# 3V3-CAN-UNISOLATED.net
KiCad netlist of a schematic drawn in Altium Designer
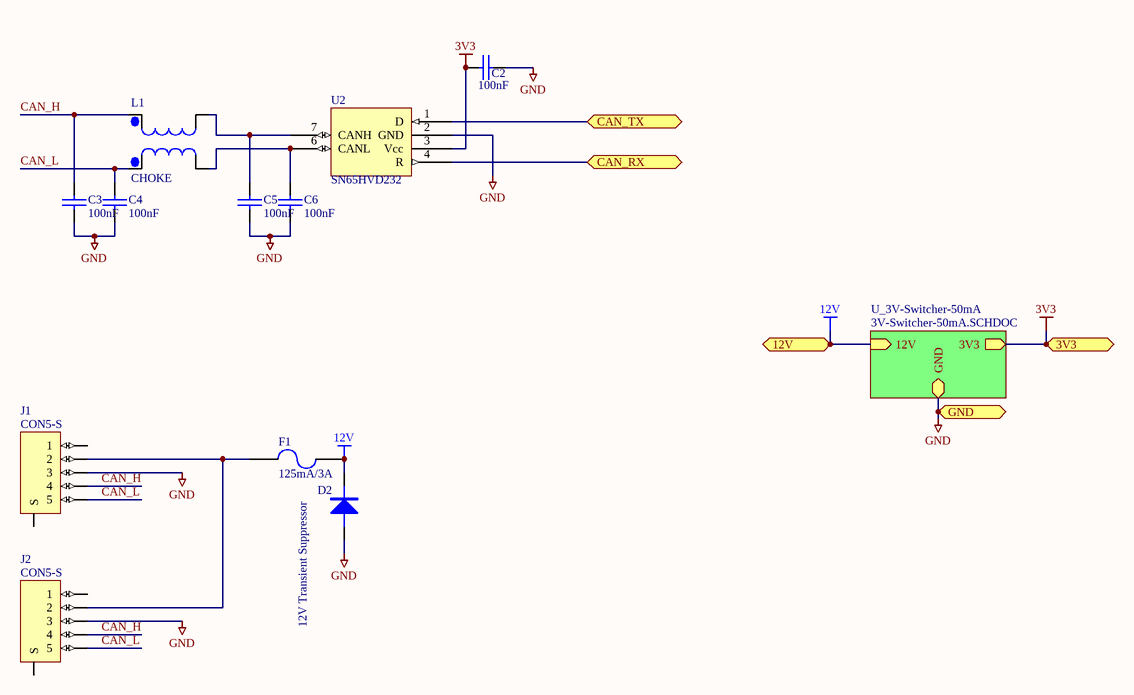
[diagram p0: 3V3-CAN-UNISOLATED.SchDoc]

(export (version "E")
  (design (tool "Eeschema 10.0.6"))
  (components
    (comp (ref "C2")
      (value "100nF")
      (footprint "0603")
      (description "Capacitor")
      (libsource (lib "*") (part "CAP"))
    )
    (comp (ref "C3")
      (value "100nF")
      (footprint "0603")
      (description "Capacitor")
      (libsource (lib "*") (part "CAP"))
    )
    (comp (ref "C4")
      (value "100nF")
      (footprint "0603")
      (description "Capacitor")
      (libsource (lib "*") (part "CAP"))
    )
    (comp (ref "C5")
      (value "100nF")
      (footprint "0603")
      (description "Capacitor")
      (libsource (lib "*") (part "CAP"))
    )
    (comp (ref "C6")
      (value "100nF")
      (footprint "0603")
      (description "Capacitor")
      (libsource (lib "*") (part "CAP"))
    )
    (comp (ref "D2")
      (value "12V Transient Suppressor")
      (footprint "SMA")
      (description "Diode")
      (libsource (lib "RCLDQ") (part "DIODE"))
    )
    (comp (ref "F1")
      (value "125mA/3A")
      (footprint "LITTELFUSE-154")
      (description "Fuse")
      (libsource (lib "*") (part "FUSE2"))
    )
    (comp (ref "J1")
      (value "CON5-S")
      (footprint "TRIAD5F")
      (description "Connector, 2 pin, with shield @ S")
      (libsource (lib "*") (part "CON5-S"))
    )
    (comp (ref "J2")
      (value "CON5-S")
      (footprint "TRIAD5F")
      (description "Connector, 2 pin, with shield @ S")
      (libsource (lib "*") (part "CON5-S"))
    )
    (comp (ref "L1") (value "CHOKE") (footprint "Epcos-Choke") (libsource (lib "RCLDQ") (part "CHOKE")))
    (comp (ref "U2")
      (value "SN65HVD232")
      (footprint "SO8")
      (description "3.3V CAN Transciever")
      (libsource (lib "*") (part "SN65HVD232"))
    )
  )
  (nets
    (net (code "1") (name "/CAN_H") (class "Default")
      (node (ref "C3") (pin "2") (pinfunction "2_2") (pintype "passive"))
      (node (ref "J1") (pin "4") (pinfunction "4_4") (pintype "bidirectional"))
      (node (ref "J2") (pin "4") (pinfunction "4_4") (pintype "bidirectional"))
      (node (ref "L1") (pin "1") (pinfunction "1_1") (pintype "passive"))
    )
    (net (code "2") (name "/CAN_L") (class "Default")
      (node (ref "C4") (pin "1") (pinfunction "1_1") (pintype "passive"))
      (node (ref "J1") (pin "5") (pinfunction "5_5") (pintype "bidirectional"))
      (node (ref "J2") (pin "5") (pinfunction "5_5") (pintype "bidirectional"))
      (node (ref "L1") (pin "2") (pinfunction "2_2") (pintype "passive"))
    )
    (net (code "3") (name "/CAN_RX") (class "Default")
      (node (ref "U2") (pin "4") (pinfunction "R_4") (pintype "output"))
    )
    (net (code "4") (name "/CAN_TX") (class "Default")
      (node (ref "U2") (pin "1") (pinfunction "D_1") (pintype "input"))
    )
    (net (code "5") (name "3V3") (class "Default")
      (node (ref "C2") (pin "2") (pinfunction "2_2") (pintype "passive"))
      (node (ref "U2") (pin "3") (pinfunction "Vcc_3") (pintype "power_in"))
    )
    (net (code "6") (name "12V") (class "Default")
      (node (ref "D2") (pin "K") (pinfunction "K_K") (pintype "passive"))
      (node (ref "F1") (pin "2") (pinfunction "2_2") (pintype "passive"))
    )
    (net (code "7") (name "GND") (class "Default")
      (node (ref "C2") (pin "1") (pinfunction "1_1") (pintype "passive"))
      (node (ref "C3") (pin "1") (pinfunction "1_1") (pintype "passive"))
      (node (ref "C4") (pin "2") (pinfunction "2_2") (pintype "passive"))
      (node (ref "C5") (pin "2") (pinfunction "2_2") (pintype "passive"))
      (node (ref "C6") (pin "2") (pinfunction "2_2") (pintype "passive"))
      (node (ref "D2") (pin "A") (pinfunction "A_A") (pintype "passive"))
      (node (ref "J1") (pin "3") (pinfunction "3_3") (pintype "bidirectional"))
      (node (ref "J2") (pin "3") (pinfunction "3_3") (pintype "bidirectional"))
      (node (ref "U2") (pin "2") (pinfunction "GND_2") (pintype "power_in"))
    )
    (net (code "8") (name "Net-(F1-Pad1)") (class "Default")
      (node (ref "F1") (pin "1") (pinfunction "1_1") (pintype "passive"))
      (node (ref "J1") (pin "2") (pinfunction "2_2") (pintype "bidirectional"))
      (node (ref "J2") (pin "2") (pinfunction "2_2") (pintype "bidirectional"))
    )
    (net (code "9") (name "Net-(U2-CANH)") (class "Default")
      (node (ref "C5") (pin "1") (pinfunction "1_1") (pintype "passive"))
      (node (ref "L1") (pin "4") (pinfunction "4_4") (pintype "passive"))
      (node (ref "U2") (pin "7") (pinfunction "CANH_7") (pintype "bidirectional"))
    )
    (net (code "10") (name "Net-(U2-CANL)") (class "Default")
      (node (ref "C6") (pin "1") (pinfunction "1_1") (pintype "passive"))
      (node (ref "L1") (pin "3") (pinfunction "3_3") (pintype "passive"))
      (node (ref "U2") (pin "6") (pinfunction "CANL_6") (pintype "bidirectional"))
    )
    (net (code "11") (name "unconnected-(J1-Pad1)") (class "Default")
      (node (ref "J1") (pin "1") (pinfunction "1_1") (pintype "bidirectional"))
    )
    (net (code "12") (name "unconnected-(J1-S-Pad0)") (class "Default")
      (node (ref "J1") (pin "0") (pinfunction "S_0") (pintype "bidirectional"))
    )
    (net (code "13") (name "unconnected-(J2-Pad1)") (class "Default")
      (node (ref "J2") (pin "1") (pinfunction "1_1") (pintype "bidirectional"))
    )
    (net (code "14") (name "unconnected-(J2-S-Pad0)") (class "Default")
      (node (ref "J2") (pin "0") (pinfunction "S_0") (pintype "bidirectional"))
    )
  )
)
